# G1Tech_PowerRelay_v06.net
KiCad netlist of a schematic drawn in EAGLE
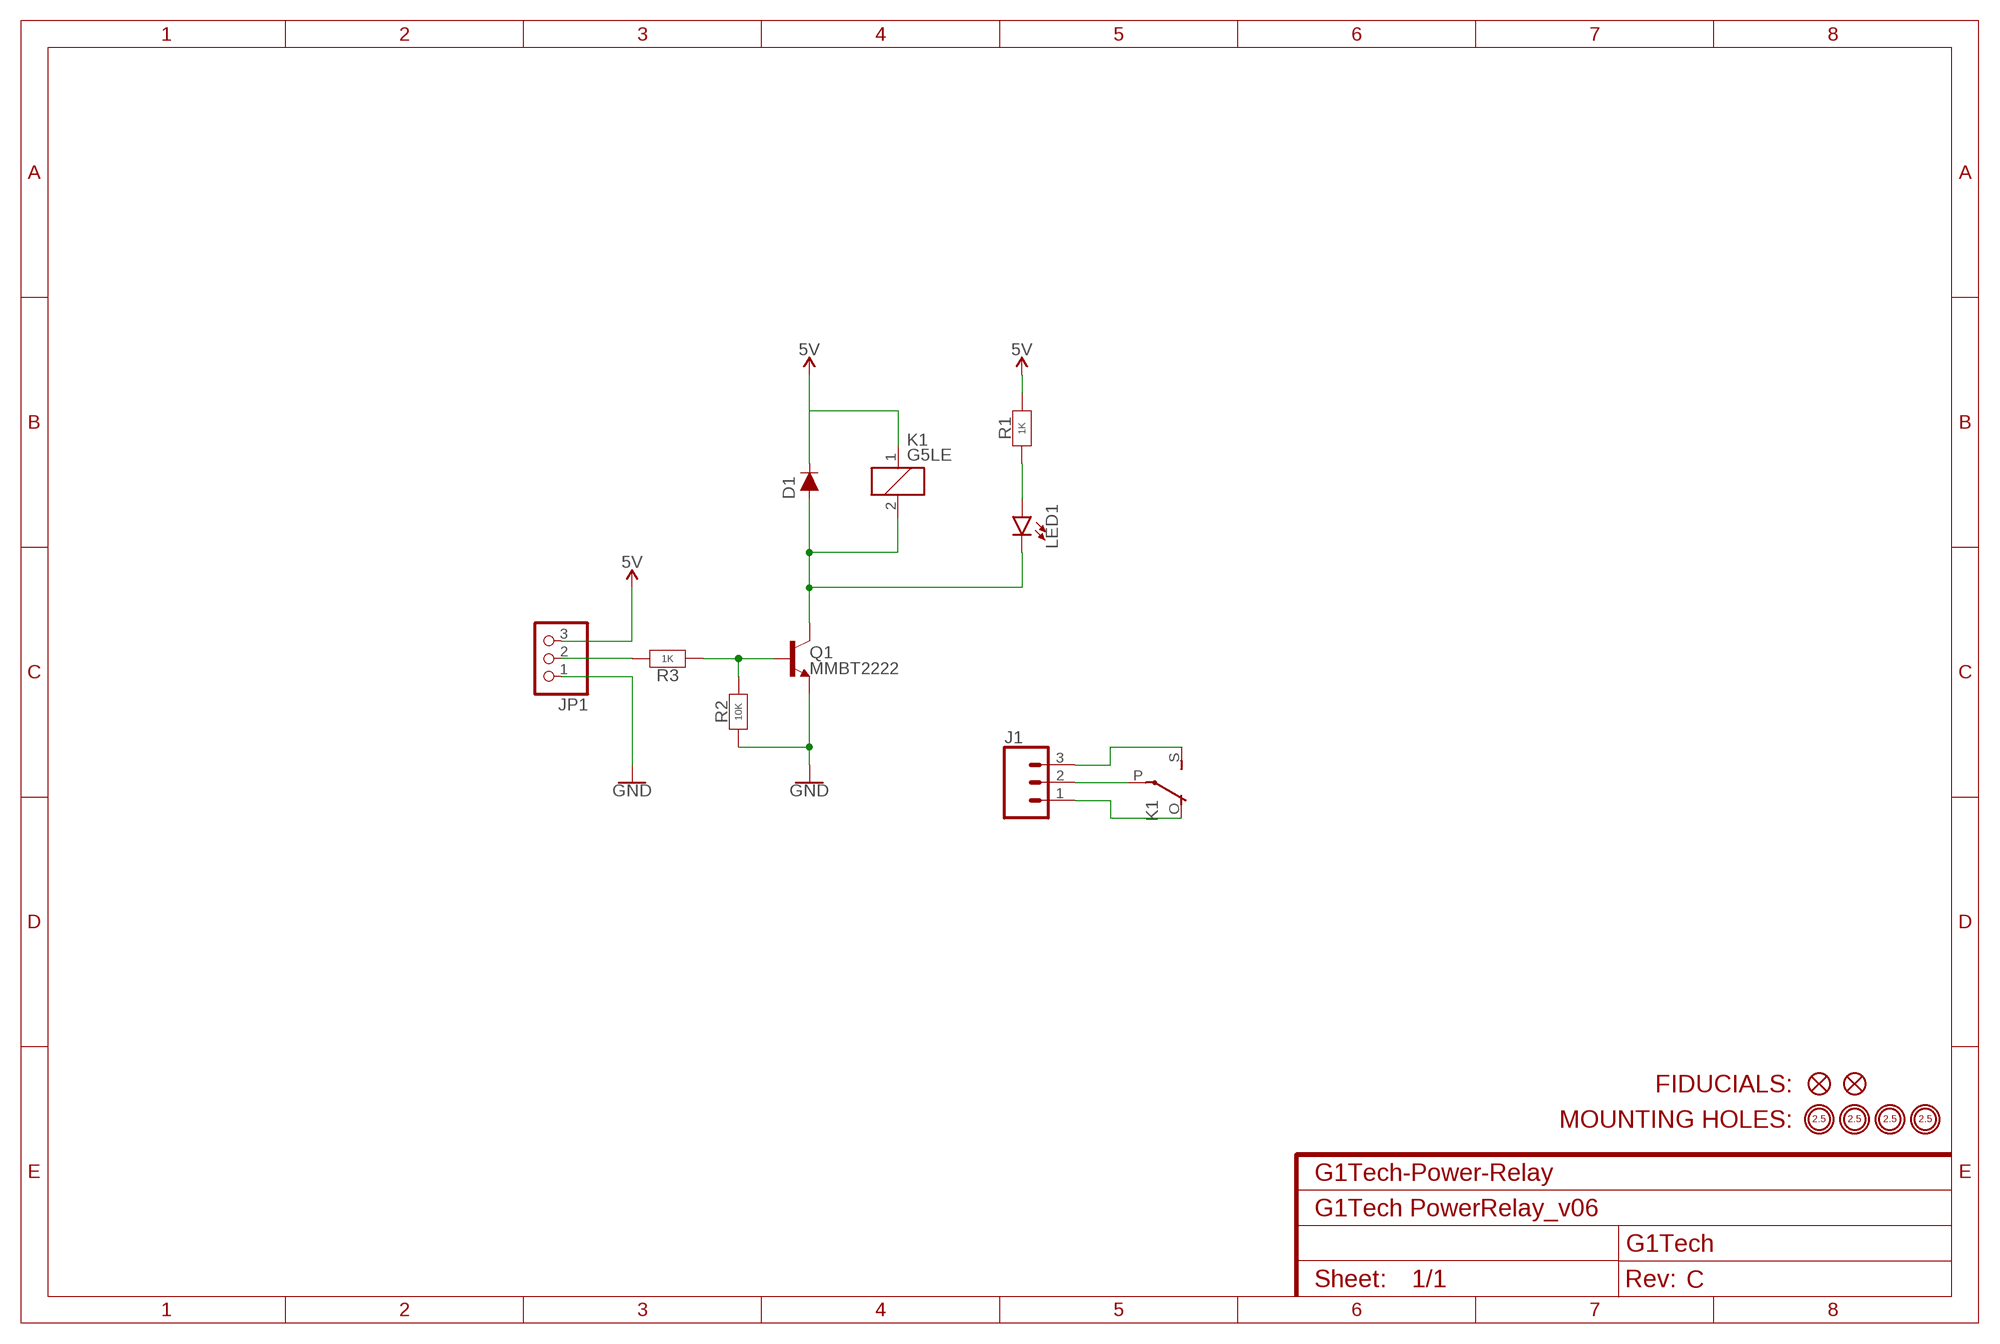
[diagram p0: schematic, sheet 1]

(export (version "E")
  (design (tool "Eeschema 10.0.6"))
  (components
    (comp (ref "D1")
      (value "DIODE-1N4148W")
      (footprint "eagle-import:SOD123")
      (libsource (lib "eagle-import") (part "DIODE-1N4148W"))
    )
    (comp (ref "FD1")
      (value "FIDUCIAL-1X2")
      (footprint "eagle-import:FIDUCIAL-1X2")
      (libsource (lib "eagle-import") (part "FIDUCIAL-1X2"))
    )
    (comp (ref "FD2")
      (value "FIDUCIAL-1X2")
      (footprint "eagle-import:FIDUCIAL-1X2")
      (libsource (lib "eagle-import") (part "FIDUCIAL-1X2"))
    )
    (comp (ref "H1")
      (value "MOUNTINGHOLE-PLATED-2.5")
      (footprint "eagle-import:MOUNTINGHOLE-PLATED-2.5")
      (libsource (lib "eagle-import") (part "MOUNTINGHOLE-PLATED-2.5"))
    )
    (comp (ref "H2")
      (value "MOUNTINGHOLE-PLATED-2.5")
      (footprint "eagle-import:MOUNTINGHOLE-PLATED-2.5")
      (libsource (lib "eagle-import") (part "MOUNTINGHOLE-PLATED-2.5"))
    )
    (comp (ref "H3")
      (value "MOUNTINGHOLE-PLATED-2.5")
      (footprint "eagle-import:MOUNTINGHOLE-PLATED-2.5")
      (libsource (lib "eagle-import") (part "MOUNTINGHOLE-PLATED-2.5"))
    )
    (comp (ref "H4")
      (value "MOUNTINGHOLE-PLATED-2.5")
      (footprint "eagle-import:MOUNTINGHOLE-PLATED-2.5")
      (libsource (lib "eagle-import") (part "MOUNTINGHOLE-PLATED-2.5"))
    )
    (comp (ref "J1")
      (value "CONN_03-SCREW-5MM")
      (footprint "eagle-import:SCREWTERMINAL-5MM-3")
      (libsource (lib "eagle-import") (part "CONN_03-SCREW-5MM"))
    )
    (comp (ref "JP1")
      (value "PINHD-1X3")
      (footprint "eagle-import:1X03")
      (libsource (lib "eagle-import") (part "PINHD-1X3"))
    )
    (comp (ref "K1")
      (value "G5LE")
      (footprint "eagle-import:G5LE")
      (libsource (lib "eagle-import") (part "G5LE"))
    )
    (comp (ref "LED1")
      (value "LED0805")
      (footprint "eagle-import:LED0805")
      (libsource (lib "eagle-import") (part "LED0805"))
    )
    (comp (ref "Q1")
      (value "MMBT2222")
      (footprint "eagle-import:SOT23-3")
      (libsource (lib "eagle-import") (part "TRANS-NPN-MMBT2222"))
    )
    (comp (ref "R1")
      (value "1K")
      (footprint "eagle-import:YAGEO-R0603")
      (libsource (lib "eagle-import") (part "YAGEO-R0603"))
    )
    (comp (ref "R2")
      (value "10K")
      (footprint "eagle-import:YAGEO-R0603")
      (libsource (lib "eagle-import") (part "YAGEO-R0603"))
    )
    (comp (ref "R3")
      (value "1K")
      (footprint "eagle-import:YAGEO-R0603")
      (libsource (lib "eagle-import") (part "YAGEO-R0603"))
    )
  )
  (nets
    (net (code "1") (name "5V") (class "Default")
      (node (ref "D1") (pin "C") (pinfunction "C_C") (pintype "passive"))
      (node (ref "JP1") (pin "3") (pinfunction "3_3") (pintype "passive"))
      (node (ref "K1") (pin "1") (pinfunction "1_1") (pintype "passive"))
      (node (ref "R1") (pin "2") (pinfunction "2_2") (pintype "passive"))
    )
    (net (code "2") (name "GND") (class "Default")
      (node (ref "JP1") (pin "1") (pinfunction "1_1") (pintype "passive"))
      (node (ref "Q1") (pin "2") (pinfunction "E_2") (pintype "passive"))
      (node (ref "R2") (pin "1") (pinfunction "1_1") (pintype "passive"))
    )
    (net (code "3") (name "Net-(J1-Pad1)") (class "Default")
      (node (ref "J1") (pin "1") (pinfunction "1_1") (pintype "passive"))
      (node (ref "K1") (pin "O") (pinfunction "O_O") (pintype "passive"))
    )
    (net (code "4") (name "Net-(J1-Pad2)") (class "Default")
      (node (ref "J1") (pin "2") (pinfunction "2_2") (pintype "passive"))
      (node (ref "K1") (pin "P") (pinfunction "P_P") (pintype "passive"))
    )
    (net (code "5") (name "Net-(J1-Pad3)") (class "Default")
      (node (ref "J1") (pin "3") (pinfunction "3_3") (pintype "passive"))
      (node (ref "K1") (pin "S") (pinfunction "S_S") (pintype "passive"))
    )
    (net (code "6") (name "Net-(JP1-Pad2)") (class "Default")
      (node (ref "JP1") (pin "2") (pinfunction "2_2") (pintype "passive"))
      (node (ref "R3") (pin "2") (pinfunction "2_2") (pintype "passive"))
    )
    (net (code "7") (name "Net-(LED1-PadA)") (class "Default")
      (node (ref "LED1") (pin "A") (pinfunction "A_A") (pintype "passive"))
      (node (ref "R1") (pin "1") (pinfunction "1_1") (pintype "passive"))
    )
    (net (code "8") (name "Net-(Q1-B)") (class "Default")
      (node (ref "Q1") (pin "1") (pinfunction "B_1") (pintype "passive"))
      (node (ref "R2") (pin "2") (pinfunction "2_2") (pintype "passive"))
      (node (ref "R3") (pin "1") (pinfunction "1_1") (pintype "passive"))
    )
    (net (code "9") (name "Net-(Q1-C)") (class "Default")
      (node (ref "D1") (pin "A") (pinfunction "A_A") (pintype "passive"))
      (node (ref "K1") (pin "2") (pinfunction "2_2") (pintype "passive"))
      (node (ref "LED1") (pin "C") (pinfunction "C_C") (pintype "passive"))
      (node (ref "Q1") (pin "3") (pinfunction "C_3") (pintype "passive"))
    )
  )
)
